# Current_Sensing.net
KiCad netlist of a schematic drawn in Altium Designer
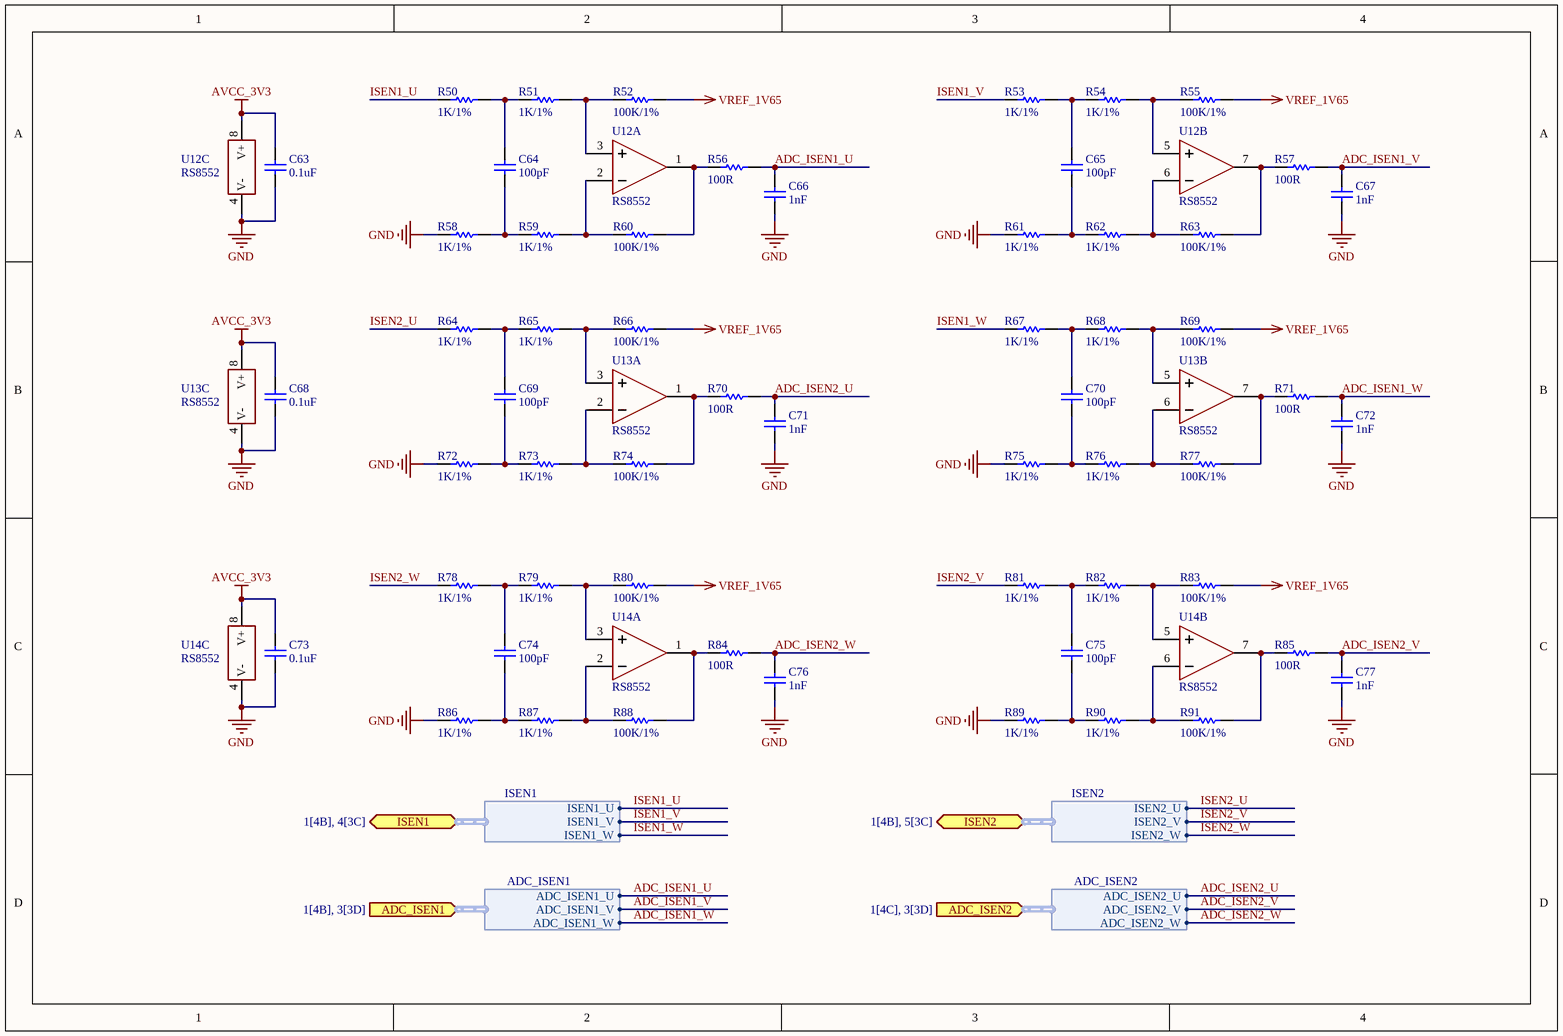
[diagram p0: Current_Sensing.SchDoc]

(export (version "E")
  (design (tool "Eeschema 10.0.6"))
  (components
    (comp (ref "C63")
      (value "0.1uF")
      (footprint "C0603_NS")
      (description "Capacitor")
      (libsource (lib "Miscellaneous Devices") (part "Cap"))
    )
    (comp (ref "C64")
      (value "100pF")
      (footprint "C0603_NS")
      (description "Capacitor")
      (libsource (lib "Miscellaneous Devices") (part "Cap"))
    )
    (comp (ref "C65")
      (value "100pF")
      (footprint "C0603_NS")
      (description "Capacitor")
      (libsource (lib "Miscellaneous Devices") (part "Cap"))
    )
    (comp (ref "C66")
      (value "1nF")
      (footprint "C0603_NS")
      (description "Capacitor")
      (libsource (lib "Miscellaneous Devices") (part "Cap"))
    )
    (comp (ref "C67")
      (value "1nF")
      (footprint "C0603_NS")
      (description "Capacitor")
      (libsource (lib "Miscellaneous Devices") (part "Cap"))
    )
    (comp (ref "C68")
      (value "0.1uF")
      (footprint "C0603_NS")
      (description "Capacitor")
      (libsource (lib "Miscellaneous Devices") (part "Cap"))
    )
    (comp (ref "C69")
      (value "100pF")
      (footprint "C0603_NS")
      (description "Capacitor")
      (libsource (lib "Miscellaneous Devices") (part "Cap"))
    )
    (comp (ref "C70")
      (value "100pF")
      (footprint "C0603_NS")
      (description "Capacitor")
      (libsource (lib "Miscellaneous Devices") (part "Cap"))
    )
    (comp (ref "C71")
      (value "1nF")
      (footprint "C0603_NS")
      (description "Capacitor")
      (libsource (lib "Miscellaneous Devices") (part "Cap"))
    )
    (comp (ref "C72")
      (value "1nF")
      (footprint "C0603_NS")
      (description "Capacitor")
      (libsource (lib "Miscellaneous Devices") (part "Cap"))
    )
    (comp (ref "C73")
      (value "0.1uF")
      (footprint "C0603_NS")
      (description "Capacitor")
      (libsource (lib "Miscellaneous Devices") (part "Cap"))
    )
    (comp (ref "C74")
      (value "100pF")
      (footprint "C0603_NS")
      (description "Capacitor")
      (libsource (lib "Miscellaneous Devices") (part "Cap"))
    )
    (comp (ref "C75")
      (value "100pF")
      (footprint "C0603_NS")
      (description "Capacitor")
      (libsource (lib "Miscellaneous Devices") (part "Cap"))
    )
    (comp (ref "C76")
      (value "1nF")
      (footprint "C0603_NS")
      (description "Capacitor")
      (libsource (lib "Miscellaneous Devices") (part "Cap"))
    )
    (comp (ref "C77")
      (value "1nF")
      (footprint "C0603_NS")
      (description "Capacitor")
      (libsource (lib "Miscellaneous Devices") (part "Cap"))
    )
    (comp (ref "R50")
      (value "1K/1%")
      (footprint "R0603_NS")
      (description "Resistor")
      (libsource (lib "Miscellaneous Devices") (part "Res1"))
    )
    (comp (ref "R51")
      (value "1K/1%")
      (footprint "R0603_NS")
      (description "Resistor")
      (libsource (lib "Miscellaneous Devices") (part "Res1"))
    )
    (comp (ref "R52")
      (value "100K/1%")
      (footprint "R0603_NS")
      (description "Resistor")
      (libsource (lib "Miscellaneous Devices") (part "Res1"))
    )
    (comp (ref "R53")
      (value "1K/1%")
      (footprint "R0603_NS")
      (description "Resistor")
      (libsource (lib "Miscellaneous Devices") (part "Res1"))
    )
    (comp (ref "R54")
      (value "1K/1%")
      (footprint "R0603_NS")
      (description "Resistor")
      (libsource (lib "Miscellaneous Devices") (part "Res1"))
    )
    (comp (ref "R55")
      (value "100K/1%")
      (footprint "R0603_NS")
      (description "Resistor")
      (libsource (lib "Miscellaneous Devices") (part "Res1"))
    )
    (comp (ref "R56")
      (value "100R")
      (footprint "R0603_NS")
      (description "Resistor")
      (libsource (lib "Miscellaneous Devices") (part "Res1"))
    )
    (comp (ref "R57")
      (value "100R")
      (footprint "R0603_NS")
      (description "Resistor")
      (libsource (lib "Miscellaneous Devices") (part "Res1"))
    )
    (comp (ref "R58")
      (value "1K/1%")
      (footprint "R0603_NS")
      (description "Resistor")
      (libsource (lib "Miscellaneous Devices") (part "Res1"))
    )
    (comp (ref "R59")
      (value "1K/1%")
      (footprint "R0603_NS")
      (description "Resistor")
      (libsource (lib "Miscellaneous Devices") (part "Res1"))
    )
    (comp (ref "R60")
      (value "100K/1%")
      (footprint "R0603_NS")
      (description "Resistor")
      (libsource (lib "Miscellaneous Devices") (part "Res1"))
    )
    (comp (ref "R61")
      (value "1K/1%")
      (footprint "R0603_NS")
      (description "Resistor")
      (libsource (lib "Miscellaneous Devices") (part "Res1"))
    )
    (comp (ref "R62")
      (value "1K/1%")
      (footprint "R0603_NS")
      (description "Resistor")
      (libsource (lib "Miscellaneous Devices") (part "Res1"))
    )
    (comp (ref "R63")
      (value "100K/1%")
      (footprint "R0603_NS")
      (description "Resistor")
      (libsource (lib "Miscellaneous Devices") (part "Res1"))
    )
    (comp (ref "R64")
      (value "1K/1%")
      (footprint "R0603_NS")
      (description "Resistor")
      (libsource (lib "Miscellaneous Devices") (part "Res1"))
    )
    (comp (ref "R65")
      (value "1K/1%")
      (footprint "R0603_NS")
      (description "Resistor")
      (libsource (lib "Miscellaneous Devices") (part "Res1"))
    )
    (comp (ref "R66")
      (value "100K/1%")
      (footprint "R0603_NS")
      (description "Resistor")
      (libsource (lib "Miscellaneous Devices") (part "Res1"))
    )
    (comp (ref "R67")
      (value "1K/1%")
      (footprint "R0603_NS")
      (description "Resistor")
      (libsource (lib "Miscellaneous Devices") (part "Res1"))
    )
    (comp (ref "R68")
      (value "1K/1%")
      (footprint "R0603_NS")
      (description "Resistor")
      (libsource (lib "Miscellaneous Devices") (part "Res1"))
    )
    (comp (ref "R69")
      (value "100K/1%")
      (footprint "R0603_NS")
      (description "Resistor")
      (libsource (lib "Miscellaneous Devices") (part "Res1"))
    )
    (comp (ref "R70")
      (value "100R")
      (footprint "R0603_NS")
      (description "Resistor")
      (libsource (lib "Miscellaneous Devices") (part "Res1"))
    )
    (comp (ref "R71")
      (value "100R")
      (footprint "R0603_NS")
      (description "Resistor")
      (libsource (lib "Miscellaneous Devices") (part "Res1"))
    )
    (comp (ref "R72")
      (value "1K/1%")
      (footprint "R0603_NS")
      (description "Resistor")
      (libsource (lib "Miscellaneous Devices") (part "Res1"))
    )
    (comp (ref "R73")
      (value "1K/1%")
      (footprint "R0603_NS")
      (description "Resistor")
      (libsource (lib "Miscellaneous Devices") (part "Res1"))
    )
    (comp (ref "R74")
      (value "100K/1%")
      (footprint "R0603_NS")
      (description "Resistor")
      (libsource (lib "Miscellaneous Devices") (part "Res1"))
    )
    (comp (ref "R75")
      (value "1K/1%")
      (footprint "R0603_NS")
      (description "Resistor")
      (libsource (lib "Miscellaneous Devices") (part "Res1"))
    )
    (comp (ref "R76")
      (value "1K/1%")
      (footprint "R0603_NS")
      (description "Resistor")
      (libsource (lib "Miscellaneous Devices") (part "Res1"))
    )
    (comp (ref "R77")
      (value "100K/1%")
      (footprint "R0603_NS")
      (description "Resistor")
      (libsource (lib "Miscellaneous Devices") (part "Res1"))
    )
    (comp (ref "R78")
      (value "1K/1%")
      (footprint "R0603_NS")
      (description "Resistor")
      (libsource (lib "Miscellaneous Devices") (part "Res1"))
    )
    (comp (ref "R79")
      (value "1K/1%")
      (footprint "R0603_NS")
      (description "Resistor")
      (libsource (lib "Miscellaneous Devices") (part "Res1"))
    )
    (comp (ref "R80")
      (value "100K/1%")
      (footprint "R0603_NS")
      (description "Resistor")
      (libsource (lib "Miscellaneous Devices") (part "Res1"))
    )
    (comp (ref "R81")
      (value "1K/1%")
      (footprint "R0603_NS")
      (description "Resistor")
      (libsource (lib "Miscellaneous Devices") (part "Res1"))
    )
    (comp (ref "R82")
      (value "1K/1%")
      (footprint "R0603_NS")
      (description "Resistor")
      (libsource (lib "Miscellaneous Devices") (part "Res1"))
    )
    (comp (ref "R83")
      (value "100K/1%")
      (footprint "R0603_NS")
      (description "Resistor")
      (libsource (lib "Miscellaneous Devices") (part "Res1"))
    )
    (comp (ref "R84")
      (value "100R")
      (footprint "R0603_NS")
      (description "Resistor")
      (libsource (lib "Miscellaneous Devices") (part "Res1"))
    )
    (comp (ref "R85")
      (value "100R")
      (footprint "R0603_NS")
      (description "Resistor")
      (libsource (lib "Miscellaneous Devices") (part "Res1"))
    )
    (comp (ref "R86")
      (value "1K/1%")
      (footprint "R0603_NS")
      (description "Resistor")
      (libsource (lib "Miscellaneous Devices") (part "Res1"))
    )
    (comp (ref "R87")
      (value "1K/1%")
      (footprint "R0603_NS")
      (description "Resistor")
      (libsource (lib "Miscellaneous Devices") (part "Res1"))
    )
    (comp (ref "R88")
      (value "100K/1%")
      (footprint "R0603_NS")
      (description "Resistor")
      (libsource (lib "Miscellaneous Devices") (part "Res1"))
    )
    (comp (ref "R89")
      (value "1K/1%")
      (footprint "R0603_NS")
      (description "Resistor")
      (libsource (lib "Miscellaneous Devices") (part "Res1"))
    )
    (comp (ref "R90")
      (value "1K/1%")
      (footprint "R0603_NS")
      (description "Resistor")
      (libsource (lib "Miscellaneous Devices") (part "Res1"))
    )
    (comp (ref "R91")
      (value "100K/1%")
      (footprint "R0603_NS")
      (description "Resistor")
      (libsource (lib "Miscellaneous Devices") (part "Res1"))
    )
    (comp (ref "U12") (value "RS8552") (footprint "MSOP8") (libsource (lib "my_library") (part "AD8606")))
    (comp (ref "U13") (value "RS8552") (footprint "MSOP8") (libsource (lib "my_library") (part "AD8606")))
    (comp (ref "U14") (value "RS8552") (footprint "MSOP8") (libsource (lib "my_library") (part "AD8606")))
  )
  (nets
    (net (code "5") (name "/ADC_ISEN1_U") (class "Default")
      (node (ref "C66") (pin "2") (pinfunction "2_2") (pintype "passive"))
      (node (ref "R56") (pin "2") (pinfunction "2_2") (pintype "passive"))
    )
    (net (code "6") (name "/ADC_ISEN1_V") (class "Default")
      (node (ref "C67") (pin "2") (pinfunction "2_2") (pintype "passive"))
      (node (ref "R57") (pin "2") (pinfunction "2_2") (pintype "passive"))
    )
    (net (code "7") (name "/ADC_ISEN1_W") (class "Default")
      (node (ref "C72") (pin "2") (pinfunction "2_2") (pintype "passive"))
      (node (ref "R71") (pin "2") (pinfunction "2_2") (pintype "passive"))
    )
    (net (code "8") (name "/ADC_ISEN2_U") (class "Default")
      (node (ref "C71") (pin "2") (pinfunction "2_2") (pintype "passive"))
      (node (ref "R70") (pin "2") (pinfunction "2_2") (pintype "passive"))
    )
    (net (code "9") (name "/ADC_ISEN2_V") (class "Default")
      (node (ref "C77") (pin "2") (pinfunction "2_2") (pintype "passive"))
      (node (ref "R85") (pin "2") (pinfunction "2_2") (pintype "passive"))
    )
    (net (code "10") (name "/ADC_ISEN2_W") (class "Default")
      (node (ref "C76") (pin "2") (pinfunction "2_2") (pintype "passive"))
      (node (ref "R84") (pin "2") (pinfunction "2_2") (pintype "passive"))
    )
    (net (code "11") (name "/ISEN1_U") (class "Default")
      (node (ref "R50") (pin "1") (pinfunction "1_1") (pintype "passive"))
    )
    (net (code "12") (name "/ISEN1_V") (class "Default")
      (node (ref "R53") (pin "1") (pinfunction "1_1") (pintype "passive"))
    )
    (net (code "13") (name "/ISEN1_W") (class "Default")
      (node (ref "R67") (pin "1") (pinfunction "1_1") (pintype "passive"))
    )
    (net (code "14") (name "/ISEN2_U") (class "Default")
      (node (ref "R64") (pin "1") (pinfunction "1_1") (pintype "passive"))
    )
    (net (code "15") (name "/ISEN2_V") (class "Default")
      (node (ref "R81") (pin "1") (pinfunction "1_1") (pintype "passive"))
    )
    (net (code "16") (name "/ISEN2_W") (class "Default")
      (node (ref "R78") (pin "1") (pinfunction "1_1") (pintype "passive"))
    )
    (net (code "21") (name "AVCC_3V3") (class "Default")
      (node (ref "C63") (pin "2") (pinfunction "2_2") (pintype "passive"))
      (node (ref "C68") (pin "2") (pinfunction "2_2") (pintype "passive"))
      (node (ref "C73") (pin "2") (pinfunction "2_2") (pintype "passive"))
      (node (ref "U12") (pin "8") (pinfunction "V+_8") (pintype "power_in"))
      (node (ref "U13") (pin "8") (pinfunction "V+_8") (pintype "power_in"))
      (node (ref "U14") (pin "8") (pinfunction "V+_8") (pintype "power_in"))
    )
    (net (code "22") (name "GND") (class "Default")
      (node (ref "C63") (pin "1") (pinfunction "1_1") (pintype "passive"))
      (node (ref "C66") (pin "1") (pinfunction "1_1") (pintype "passive"))
      (node (ref "C67") (pin "1") (pinfunction "1_1") (pintype "passive"))
      (node (ref "C68") (pin "1") (pinfunction "1_1") (pintype "passive"))
      (node (ref "C71") (pin "1") (pinfunction "1_1") (pintype "passive"))
      (node (ref "C72") (pin "1") (pinfunction "1_1") (pintype "passive"))
      (node (ref "C73") (pin "1") (pinfunction "1_1") (pintype "passive"))
      (node (ref "C76") (pin "1") (pinfunction "1_1") (pintype "passive"))
      (node (ref "C77") (pin "1") (pinfunction "1_1") (pintype "passive"))
      (node (ref "R58") (pin "1") (pinfunction "1_1") (pintype "passive"))
      (node (ref "R61") (pin "1") (pinfunction "1_1") (pintype "passive"))
      (node (ref "R72") (pin "1") (pinfunction "1_1") (pintype "passive"))
      (node (ref "R75") (pin "1") (pinfunction "1_1") (pintype "passive"))
      (node (ref "R86") (pin "1") (pinfunction "1_1") (pintype "passive"))
      (node (ref "R89") (pin "1") (pinfunction "1_1") (pintype "passive"))
      (node (ref "U12") (pin "4") (pinfunction "V-_4") (pintype "power_in"))
      (node (ref "U13") (pin "4") (pinfunction "V-_4") (pintype "power_in"))
      (node (ref "U14") (pin "4") (pinfunction "V-_4") (pintype "power_in"))
    )
    (net (code "23") (name "Net-(C64-Pad1)") (class "Default")
      (node (ref "C64") (pin "1") (pinfunction "1_1") (pintype "passive"))
      (node (ref "R58") (pin "2") (pinfunction "2_2") (pintype "passive"))
      (node (ref "R59") (pin "1") (pinfunction "1_1") (pintype "passive"))
    )
    (net (code "24") (name "Net-(C64-Pad2)") (class "Default")
      (node (ref "C64") (pin "2") (pinfunction "2_2") (pintype "passive"))
      (node (ref "R50") (pin "2") (pinfunction "2_2") (pintype "passive"))
      (node (ref "R51") (pin "1") (pinfunction "1_1") (pintype "passive"))
    )
    (net (code "25") (name "Net-(C65-Pad1)") (class "Default")
      (node (ref "C65") (pin "1") (pinfunction "1_1") (pintype "passive"))
      (node (ref "R61") (pin "2") (pinfunction "2_2") (pintype "passive"))
      (node (ref "R62") (pin "1") (pinfunction "1_1") (pintype "passive"))
    )
    (net (code "26") (name "Net-(C65-Pad2)") (class "Default")
      (node (ref "C65") (pin "2") (pinfunction "2_2") (pintype "passive"))
      (node (ref "R53") (pin "2") (pinfunction "2_2") (pintype "passive"))
      (node (ref "R54") (pin "1") (pinfunction "1_1") (pintype "passive"))
    )
    (net (code "27") (name "Net-(C69-Pad1)") (class "Default")
      (node (ref "C69") (pin "1") (pinfunction "1_1") (pintype "passive"))
      (node (ref "R72") (pin "2") (pinfunction "2_2") (pintype "passive"))
      (node (ref "R73") (pin "1") (pinfunction "1_1") (pintype "passive"))
    )
    (net (code "28") (name "Net-(C69-Pad2)") (class "Default")
      (node (ref "C69") (pin "2") (pinfunction "2_2") (pintype "passive"))
      (node (ref "R64") (pin "2") (pinfunction "2_2") (pintype "passive"))
      (node (ref "R65") (pin "1") (pinfunction "1_1") (pintype "passive"))
    )
    (net (code "29") (name "Net-(C70-Pad1)") (class "Default")
      (node (ref "C70") (pin "1") (pinfunction "1_1") (pintype "passive"))
      (node (ref "R75") (pin "2") (pinfunction "2_2") (pintype "passive"))
      (node (ref "R76") (pin "1") (pinfunction "1_1") (pintype "passive"))
    )
    (net (code "30") (name "Net-(C70-Pad2)") (class "Default")
      (node (ref "C70") (pin "2") (pinfunction "2_2") (pintype "passive"))
      (node (ref "R67") (pin "2") (pinfunction "2_2") (pintype "passive"))
      (node (ref "R68") (pin "1") (pinfunction "1_1") (pintype "passive"))
    )
    (net (code "31") (name "Net-(C74-Pad1)") (class "Default")
      (node (ref "C74") (pin "1") (pinfunction "1_1") (pintype "passive"))
      (node (ref "R86") (pin "2") (pinfunction "2_2") (pintype "passive"))
      (node (ref "R87") (pin "1") (pinfunction "1_1") (pintype "passive"))
    )
    (net (code "32") (name "Net-(C74-Pad2)") (class "Default")
      (node (ref "C74") (pin "2") (pinfunction "2_2") (pintype "passive"))
      (node (ref "R78") (pin "2") (pinfunction "2_2") (pintype "passive"))
      (node (ref "R79") (pin "1") (pinfunction "1_1") (pintype "passive"))
    )
    (net (code "33") (name "Net-(C75-Pad1)") (class "Default")
      (node (ref "C75") (pin "1") (pinfunction "1_1") (pintype "passive"))
      (node (ref "R89") (pin "2") (pinfunction "2_2") (pintype "passive"))
      (node (ref "R90") (pin "1") (pinfunction "1_1") (pintype "passive"))
    )
    (net (code "34") (name "Net-(C75-Pad2)") (class "Default")
      (node (ref "C75") (pin "2") (pinfunction "2_2") (pintype "passive"))
      (node (ref "R81") (pin "2") (pinfunction "2_2") (pintype "passive"))
      (node (ref "R82") (pin "1") (pinfunction "1_1") (pintype "passive"))
    )
    (net (code "35") (name "Net-(U12A-+IN_A)") (class "Default")
      (node (ref "R51") (pin "2") (pinfunction "2_2") (pintype "passive"))
      (node (ref "R52") (pin "1") (pinfunction "1_1") (pintype "passive"))
      (node (ref "U12") (pin "3") (pinfunction "+IN_A_3") (pintype "passive"))
    )
    (net (code "36") (name "Net-(U12A--IN_A)") (class "Default")
      (node (ref "R59") (pin "2") (pinfunction "2_2") (pintype "passive"))
      (node (ref "R60") (pin "1") (pinfunction "1_1") (pintype "passive"))
      (node (ref "U12") (pin "2") (pinfunction "-IN_A_2") (pintype "passive"))
    )
    (net (code "37") (name "Net-(U12A-OUT_A)") (class "Default")
      (node (ref "R56") (pin "1") (pinfunction "1_1") (pintype "passive"))
      (node (ref "R60") (pin "2") (pinfunction "2_2") (pintype "passive"))
      (node (ref "U12") (pin "1") (pinfunction "OUT_A_1") (pintype "passive"))
    )
    (net (code "38") (name "Net-(U12B-+IN_B)") (class "Default")
      (node (ref "R54") (pin "2") (pinfunction "2_2") (pintype "passive"))
      (node (ref "R55") (pin "1") (pinfunction "1_1") (pintype "passive"))
      (node (ref "U12") (pin "5") (pinfunction "+IN_B_5") (pintype "passive"))
    )
    (net (code "39") (name "Net-(U12B--IN_B)") (class "Default")
      (node (ref "R62") (pin "2") (pinfunction "2_2") (pintype "passive"))
      (node (ref "R63") (pin "1") (pinfunction "1_1") (pintype "passive"))
      (node (ref "U12") (pin "6") (pinfunction "-IN_B_6") (pintype "passive"))
    )
    (net (code "40") (name "Net-(U12B-OUT_B)") (class "Default")
      (node (ref "R57") (pin "1") (pinfunction "1_1") (pintype "passive"))
      (node (ref "R63") (pin "2") (pinfunction "2_2") (pintype "passive"))
      (node (ref "U12") (pin "7") (pinfunction "OUT_B_7") (pintype "passive"))
    )
    (net (code "41") (name "Net-(U13A-+IN_A)") (class "Default")
      (node (ref "R65") (pin "2") (pinfunction "2_2") (pintype "passive"))
      (node (ref "R66") (pin "1") (pinfunction "1_1") (pintype "passive"))
      (node (ref "U13") (pin "3") (pinfunction "+IN_A_3") (pintype "passive"))
    )
    (net (code "42") (name "Net-(U13A--IN_A)") (class "Default")
      (node (ref "R73") (pin "2") (pinfunction "2_2") (pintype "passive"))
      (node (ref "R74") (pin "1") (pinfunction "1_1") (pintype "passive"))
      (node (ref "U13") (pin "2") (pinfunction "-IN_A_2") (pintype "passive"))
    )
    (net (code "43") (name "Net-(U13A-OUT_A)") (class "Default")
      (node (ref "R70") (pin "1") (pinfunction "1_1") (pintype "passive"))
      (node (ref "R74") (pin "2") (pinfunction "2_2") (pintype "passive"))
      (node (ref "U13") (pin "1") (pinfunction "OUT_A_1") (pintype "passive"))
    )
    (net (code "44") (name "Net-(U13B-+IN_B)") (class "Default")
      (node (ref "R68") (pin "2") (pinfunction "2_2") (pintype "passive"))
      (node (ref "R69") (pin "1") (pinfunction "1_1") (pintype "passive"))
      (node (ref "U13") (pin "5") (pinfunction "+IN_B_5") (pintype "passive"))
    )
    (net (code "45") (name "Net-(U13B--IN_B)") (class "Default")
      (node (ref "R76") (pin "2") (pinfunction "2_2") (pintype "passive"))
      (node (ref "R77") (pin "1") (pinfunction "1_1") (pintype "passive"))
      (node (ref "U13") (pin "6") (pinfunction "-IN_B_6") (pintype "passive"))
    )
    (net (code "46") (name "Net-(U13B-OUT_B)") (class "Default")
      (node (ref "R71") (pin "1") (pinfunction "1_1") (pintype "passive"))
      (node (ref "R77") (pin "2") (pinfunction "2_2") (pintype "passive"))
      (node (ref "U13") (pin "7") (pinfunction "OUT_B_7") (pintype "passive"))
    )
    (net (code "47") (name "Net-(U14A-+IN_A)") (class "Default")
      (node (ref "R79") (pin "2") (pinfunction "2_2") (pintype "passive"))
      (node (ref "R80") (pin "1") (pinfunction "1_1") (pintype "passive"))
      (node (ref "U14") (pin "3") (pinfunction "+IN_A_3") (pintype "passive"))
    )
    (net (code "48") (name "Net-(U14A--IN_A)") (class "Default")
      (node (ref "R87") (pin "2") (pinfunction "2_2") (pintype "passive"))
      (node (ref "R88") (pin "1") (pinfunction "1_1") (pintype "passive"))
      (node (ref "U14") (pin "2") (pinfunction "-IN_A_2") (pintype "passive"))
    )
    (net (code "49") (name "Net-(U14A-OUT_A)") (class "Default")
      (node (ref "R84") (pin "1") (pinfunction "1_1") (pintype "passive"))
      (node (ref "R88") (pin "2") (pinfunction "2_2") (pintype "passive"))
      (node (ref "U14") (pin "1") (pinfunction "OUT_A_1") (pintype "passive"))
    )
    (net (code "50") (name "Net-(U14B-+IN_B)") (class "Default")
      (node (ref "R82") (pin "2") (pinfunction "2_2") (pintype "passive"))
      (node (ref "R83") (pin "1") (pinfunction "1_1") (pintype "passive"))
      (node (ref "U14") (pin "5") (pinfunction "+IN_B_5") (pintype "passive"))
    )
    (net (code "51") (name "Net-(U14B--IN_B)") (class "Default")
      (node (ref "R90") (pin "2") (pinfunction "2_2") (pintype "passive"))
      (node (ref "R91") (pin "1") (pinfunction "1_1") (pintype "passive"))
      (node (ref "U14") (pin "6") (pinfunction "-IN_B_6") (pintype "passive"))
    )
    (net (code "52") (name "Net-(U14B-OUT_B)") (class "Default")
      (node (ref "R85") (pin "1") (pinfunction "1_1") (pintype "passive"))
      (node (ref "R91") (pin "2") (pinfunction "2_2") (pintype "passive"))
      (node (ref "U14") (pin "7") (pinfunction "OUT_B_7") (pintype "passive"))
    )
    (net (code "53") (name "VREF_1V65") (class "Default")
      (node (ref "R52") (pin "2") (pinfunction "2_2") (pintype "passive"))
      (node (ref "R55") (pin "2") (pinfunction "2_2") (pintype "passive"))
      (node (ref "R66") (pin "2") (pinfunction "2_2") (pintype "passive"))
      (node (ref "R69") (pin "2") (pinfunction "2_2") (pintype "passive"))
      (node (ref "R80") (pin "2") (pinfunction "2_2") (pintype "passive"))
      (node (ref "R83") (pin "2") (pinfunction "2_2") (pintype "passive"))
    )
  )
)
